# tridev.net
KiCad netlist of a schematic drawn in EAGLE
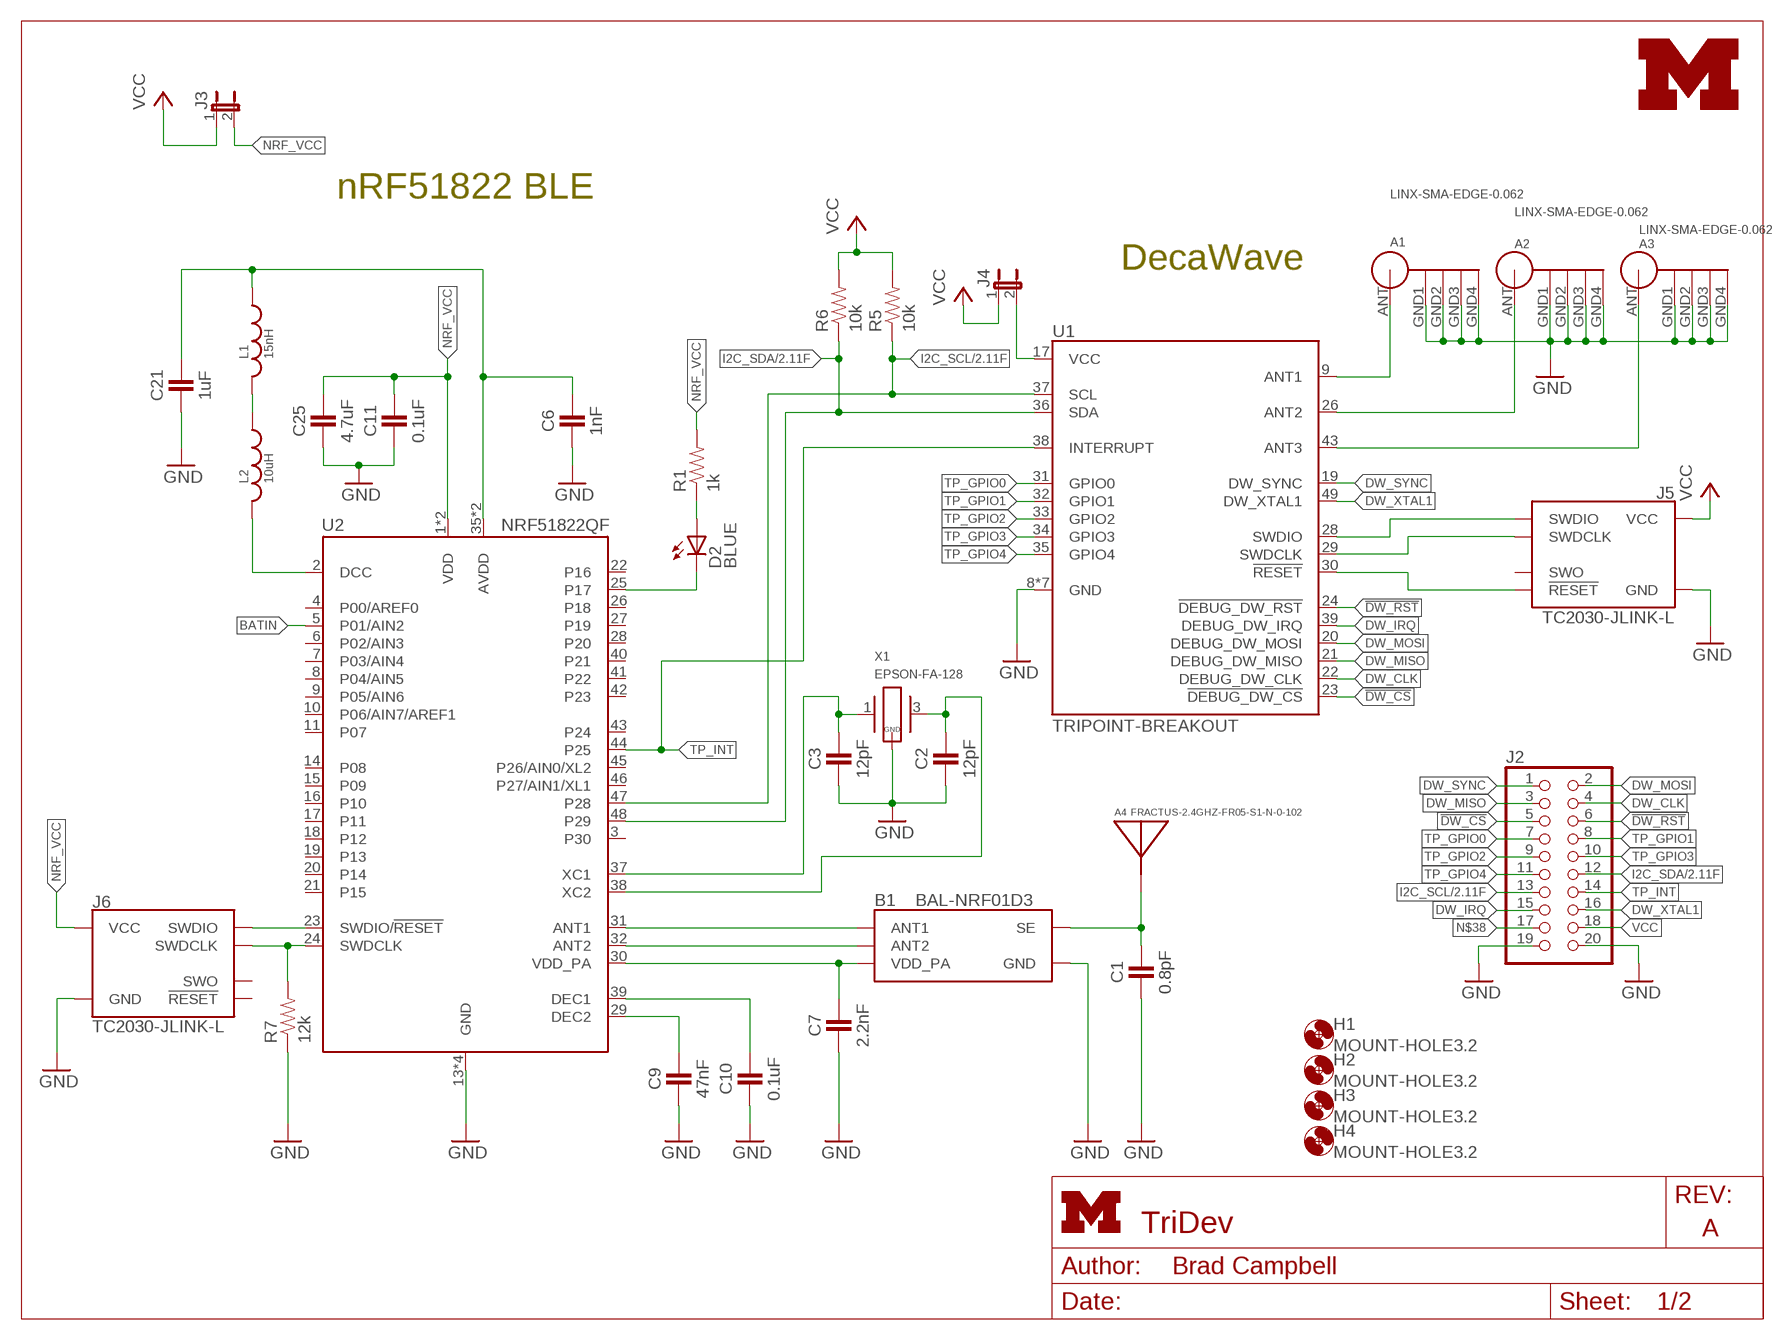
[diagram p0: schematic, sheet 1]
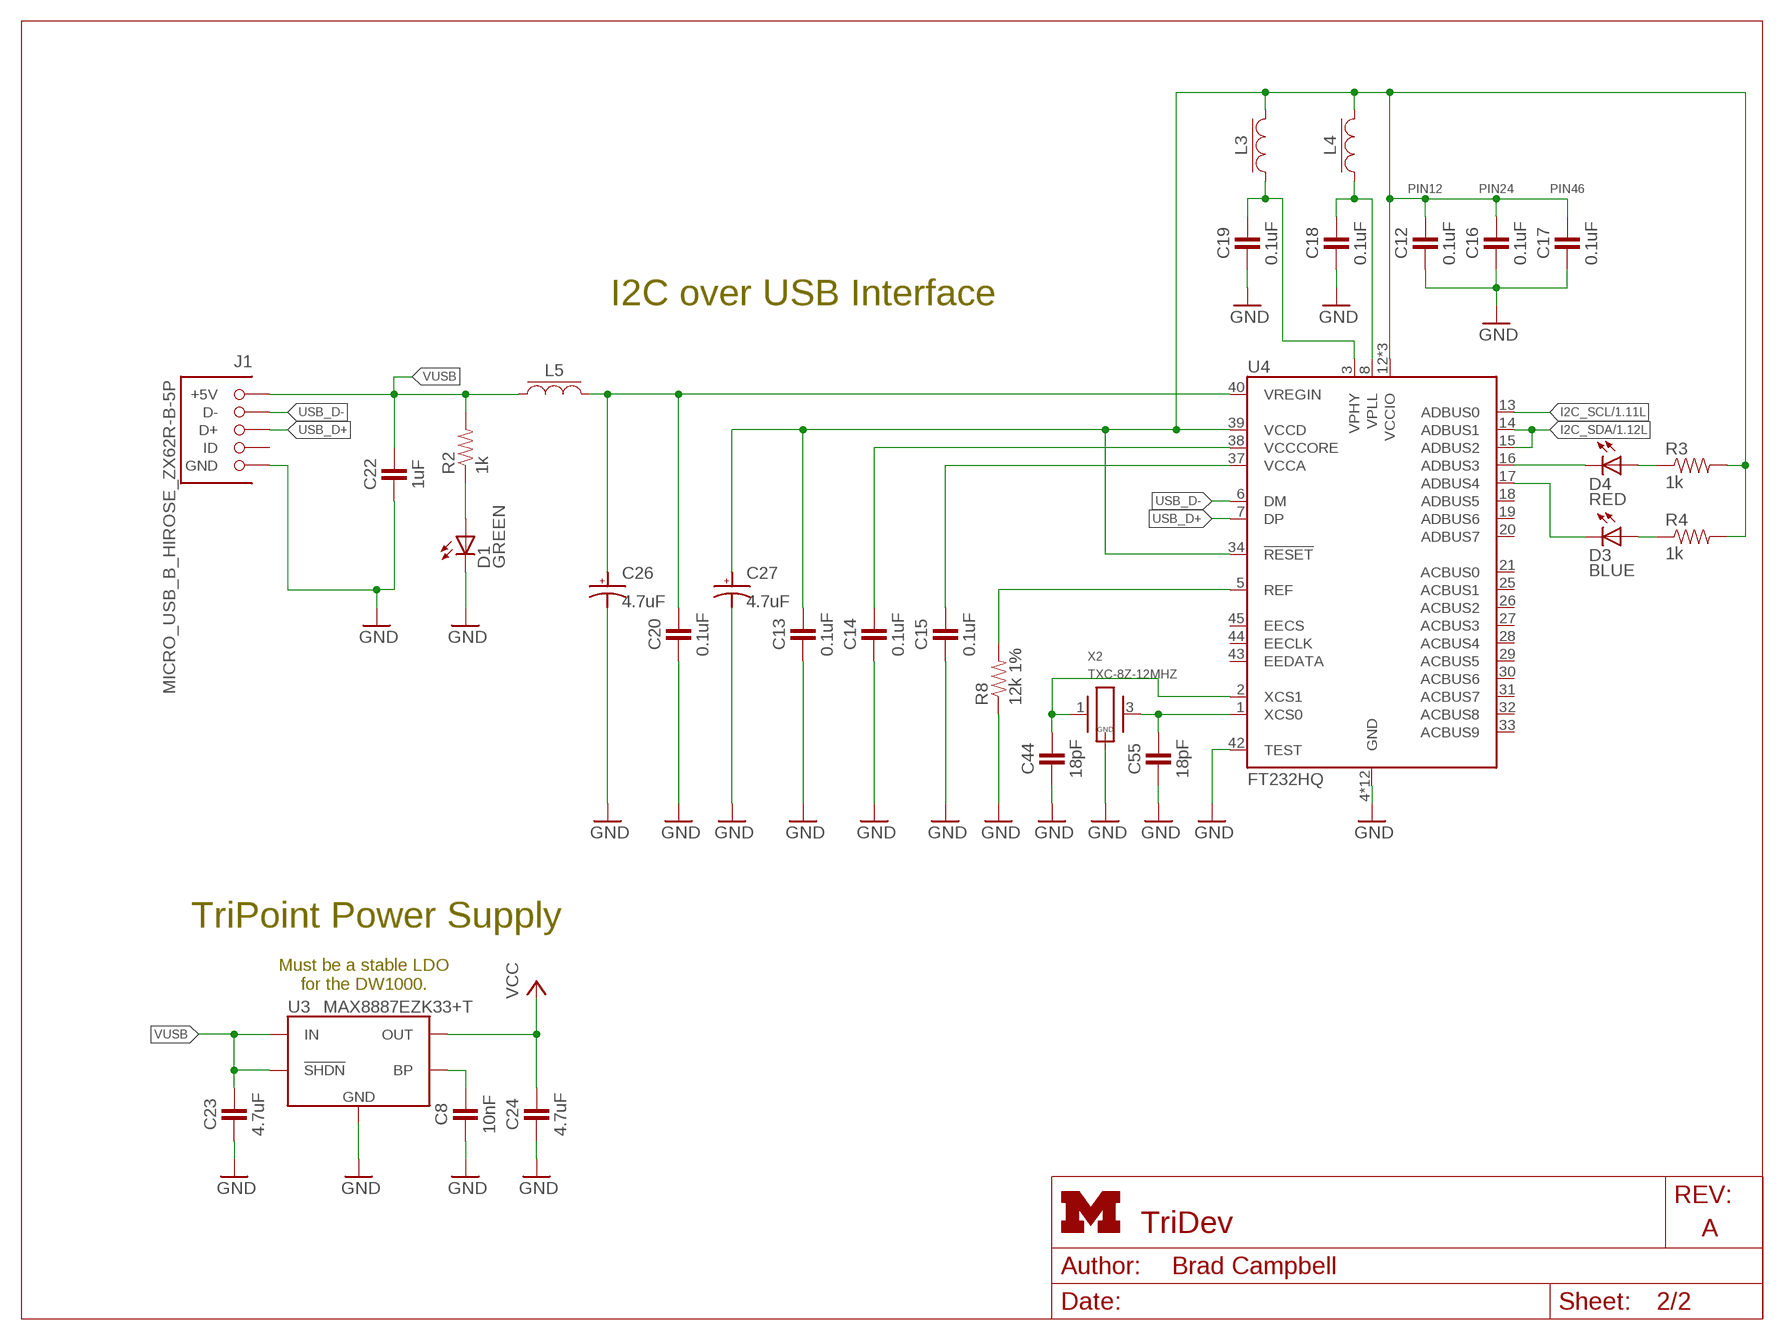
[diagram p1: schematic, sheet 2]

(export (version "E")
  (design (tool "Eeschema 10.0.6"))
  (components
    (comp (ref "A1")
      (value "LINX-SMA-EDGE-0.062")
      (footprint "eagle-import:CONSMA003.062")
      (libsource (lib "eagle-import") (part "LINX-SMA-EDGE-0.062"))
    )
    (comp (ref "A2")
      (value "LINX-SMA-EDGE-0.062")
      (footprint "eagle-import:CONSMA003.062")
      (libsource (lib "eagle-import") (part "LINX-SMA-EDGE-0.062"))
    )
    (comp (ref "A3")
      (value "LINX-SMA-EDGE-0.062")
      (footprint "eagle-import:CONSMA003.062")
      (libsource (lib "eagle-import") (part "LINX-SMA-EDGE-0.062"))
    )
    (comp (ref "A4")
      (value "FRACTUS-2.4GHZ-FR05-S1-N-0-102")
      (footprint "eagle-import:FRACTUS-ANTENNA-FR05-S1-N-0-102")
      (libsource (lib "eagle-import") (part "FRACTUS-2.4GHZ-FR05-S1-N-0-102"))
    )
    (comp (ref "B1")
      (value "BAL-NRF01D3")
      (footprint "eagle-import:BAL-NRF01D3")
      (libsource (lib "eagle-import") (part "BAL-NRF01D3"))
    )
    (comp (ref "C1")
      (value "0.8pF")
      (footprint "eagle-import:0402_CAP")
      (libsource (lib "eagle-import") (part "CAPACITOR"))
    )
    (comp (ref "C2")
      (value "12pF")
      (footprint "eagle-import:0402_CAP")
      (libsource (lib "eagle-import") (part "CAPACITOR"))
    )
    (comp (ref "C3")
      (value "12pF")
      (footprint "eagle-import:0402_CAP")
      (libsource (lib "eagle-import") (part "CAPACITOR"))
    )
    (comp (ref "C6")
      (value "1nF")
      (footprint "eagle-import:0402_CAP")
      (libsource (lib "eagle-import") (part "CAPACITOR"))
    )
    (comp (ref "C7")
      (value "2.2nF")
      (footprint "eagle-import:0402_CAP")
      (libsource (lib "eagle-import") (part "CAPACITOR"))
    )
    (comp (ref "C9")
      (value "47nF")
      (footprint "eagle-import:0402_CAP")
      (libsource (lib "eagle-import") (part "CAPACITOR"))
    )
    (comp (ref "C10")
      (value "0.1uF")
      (footprint "eagle-import:0402_CAP")
      (libsource (lib "eagle-import") (part "CAPACITOR"))
    )
    (comp (ref "C11")
      (value "0.1uF")
      (footprint "eagle-import:0402_CAP")
      (libsource (lib "eagle-import") (part "CAPACITOR"))
    )
    (comp (ref "C21")
      (value "1uF")
      (footprint "eagle-import:0402_CAP")
      (libsource (lib "eagle-import") (part "CAPACITOR"))
    )
    (comp (ref "C25")
      (value "4.7uF")
      (footprint "eagle-import:0402_CAP")
      (libsource (lib "eagle-import") (part "CAPACITOR"))
    )
    (comp (ref "D2")
      (value "BLUE")
      (footprint "eagle-import:LED-0603")
      (libsource (lib "eagle-import") (part "LED0603"))
    )
    (comp (ref "H1")
      (value "MOUNT-HOLE3.2")
      (footprint "eagle-import:3,2")
      (libsource (lib "eagle-import") (part "MOUNT-HOLE3.2"))
    )
    (comp (ref "H2")
      (value "MOUNT-HOLE3.2")
      (footprint "eagle-import:3,2")
      (libsource (lib "eagle-import") (part "MOUNT-HOLE3.2"))
    )
    (comp (ref "H3")
      (value "MOUNT-HOLE3.2")
      (footprint "eagle-import:3,2")
      (libsource (lib "eagle-import") (part "MOUNT-HOLE3.2"))
    )
    (comp (ref "H4")
      (value "MOUNT-HOLE3.2")
      (footprint "eagle-import:3,2")
      (libsource (lib "eagle-import") (part "MOUNT-HOLE3.2"))
    )
    (comp (ref "J2")
      (value "PINHD-2X10")
      (footprint "eagle-import:2X10")
      (libsource (lib "eagle-import") (part "PINHD-2X10"))
    )
    (comp (ref "J3")
      (value "JUMPER-2PTH")
      (footprint "eagle-import:1X02")
      (libsource (lib "eagle-import") (part "JUMPER-2PTH"))
    )
    (comp (ref "J4")
      (value "JUMPER-2PTH")
      (footprint "eagle-import:1X02")
      (libsource (lib "eagle-import") (part "JUMPER-2PTH"))
    )
    (comp (ref "J5")
      (value "TC2030-JLINK-L")
      (footprint "eagle-import:TC2030-IDC")
      (libsource (lib "eagle-import") (part "TC2030-JLINK-L"))
    )
    (comp (ref "J6")
      (value "TC2030-JLINK-L")
      (footprint "eagle-import:TC2030-IDC")
      (libsource (lib "eagle-import") (part "TC2030-JLINK-L"))
    )
    (comp (ref "L1")
      (value "15nH")
      (footprint "eagle-import:0402_CAP")
      (libsource (lib "eagle-import") (part "INDUCTOR0402"))
    )
    (comp (ref "L2")
      (value "10uH")
      (footprint "eagle-import:0603_CAP")
      (libsource (lib "eagle-import") (part "INDUCTOR0603"))
    )
    (comp (ref "LOGO1")
      (value "UMICH_SOLID_SMALL")
      (footprint "eagle-import:UMICH_SOLID_75MIL")
      (libsource (lib "eagle-import") (part "UMICH_SOLID_SMALL"))
    )
    (comp (ref "R1")
      (value "1k")
      (footprint "eagle-import:0402_RES")
      (libsource (lib "eagle-import") (part "RESISTOR0402_RES"))
    )
    (comp (ref "R5")
      (value "10k")
      (footprint "eagle-import:0402_RES")
      (libsource (lib "eagle-import") (part "RESISTOR0402_RES"))
    )
    (comp (ref "R6")
      (value "10k")
      (footprint "eagle-import:0402_RES")
      (libsource (lib "eagle-import") (part "RESISTOR0402_RES"))
    )
    (comp (ref "R7")
      (value "12k")
      (footprint "eagle-import:0402_RES")
      (libsource (lib "eagle-import") (part "RESISTOR0402_RES"))
    )
    (comp (ref "U1")
      (value "TRIPOINT-BREAKOUT")
      (footprint "eagle-import:TRIPOINT-BREAKOUT")
      (libsource (lib "eagle-import") (part "TRIPOINT-BREAKOUT"))
    )
    (comp (ref "U2")
      (value "NRF51822QF")
      (footprint "eagle-import:QFN-48-6MM")
      (libsource (lib "eagle-import") (part "NRF51822QF"))
    )
    (comp (ref "X1")
      (value "EPSON-FA-128")
      (footprint "eagle-import:FA-128")
      (libsource (lib "eagle-import") (part "EPSON-FA-128"))
    )
    (comp (ref "C8")
      (value "10nF")
      (footprint "eagle-import:0402_CAP")
      (libsource (lib "eagle-import") (part "CAPACITOR"))
    )
    (comp (ref "C12")
      (value "0.1uF")
      (footprint "eagle-import:0402_CAP")
      (libsource (lib "eagle-import") (part "CAPACITOR"))
    )
    (comp (ref "C13")
      (value "0.1uF")
      (footprint "eagle-import:0402_CAP")
      (libsource (lib "eagle-import") (part "CAPACITOR"))
    )
    (comp (ref "C14")
      (value "0.1uF")
      (footprint "eagle-import:0402_CAP")
      (libsource (lib "eagle-import") (part "CAPACITOR"))
    )
    (comp (ref "C15")
      (value "0.1uF")
      (footprint "eagle-import:0402_CAP")
      (libsource (lib "eagle-import") (part "CAPACITOR"))
    )
    (comp (ref "C16")
      (value "0.1uF")
      (footprint "eagle-import:0402_CAP")
      (libsource (lib "eagle-import") (part "CAPACITOR"))
    )
    (comp (ref "C17")
      (value "0.1uF")
      (footprint "eagle-import:0402_CAP")
      (libsource (lib "eagle-import") (part "CAPACITOR"))
    )
    (comp (ref "C18")
      (value "0.1uF")
      (footprint "eagle-import:0402_CAP")
      (libsource (lib "eagle-import") (part "CAPACITOR"))
    )
    (comp (ref "C19")
      (value "0.1uF")
      (footprint "eagle-import:0402_CAP")
      (libsource (lib "eagle-import") (part "CAPACITOR"))
    )
    (comp (ref "C20")
      (value "0.1uF")
      (footprint "eagle-import:0402_CAP")
      (libsource (lib "eagle-import") (part "CAPACITOR"))
    )
    (comp (ref "C22")
      (value "1uF")
      (footprint "eagle-import:0402_CAP")
      (libsource (lib "eagle-import") (part "CAPACITOR"))
    )
    (comp (ref "C23")
      (value "4.7uF")
      (footprint "eagle-import:0402_CAP")
      (libsource (lib "eagle-import") (part "CAPACITOR"))
    )
    (comp (ref "C24")
      (value "4.7uF")
      (footprint "eagle-import:0402_CAP")
      (libsource (lib "eagle-import") (part "CAPACITOR"))
    )
    (comp (ref "C26")
      (value "4.7uF")
      (footprint "eagle-import:CAP0603")
      (libsource (lib "eagle-import") (part "CAP_POL0603"))
    )
    (comp (ref "C27")
      (value "4.7uF")
      (footprint "eagle-import:CAP0603")
      (libsource (lib "eagle-import") (part "CAP_POL0603"))
    )
    (comp (ref "C44")
      (value "18pF")
      (footprint "eagle-import:0402_CAP")
      (libsource (lib "eagle-import") (part "CAPACITOR"))
    )
    (comp (ref "C55")
      (value "18pF")
      (footprint "eagle-import:0402_CAP")
      (libsource (lib "eagle-import") (part "CAPACITOR"))
    )
    (comp (ref "D1")
      (value "GREEN")
      (footprint "eagle-import:LED-0603")
      (libsource (lib "eagle-import") (part "LED0603"))
    )
    (comp (ref "D3")
      (value "BLUE")
      (footprint "eagle-import:LED-0603")
      (libsource (lib "eagle-import") (part "LED0603"))
    )
    (comp (ref "D4")
      (value "RED")
      (footprint "eagle-import:LED-0603")
      (libsource (lib "eagle-import") (part "LED0603"))
    )
    (comp (ref "J1")
      (value "MICRO_USB_B_HIROSE_ZX62R-B-5P")
      (footprint "eagle-import:USB_MICRO_B-HIROSE-ZX62R-B-5P")
      (libsource (lib "eagle-import") (part "MICRO_USB_B_HIROSE_ZX62R-B-5P"))
    )
    (comp (ref "L3")
      (value "FERRITE_BEAD")
      (footprint "eagle-import:0603_CAP")
      (libsource (lib "eagle-import") (part "FERRITE_BEAD"))
    )
    (comp (ref "L4")
      (value "FERRITE_BEAD")
      (footprint "eagle-import:0603_CAP")
      (libsource (lib "eagle-import") (part "FERRITE_BEAD"))
    )
    (comp (ref "L5")
      (value "FERRITE_BEAD")
      (footprint "eagle-import:0603_CAP")
      (libsource (lib "eagle-import") (part "FERRITE_BEAD"))
    )
    (comp (ref "R2")
      (value "1k")
      (footprint "eagle-import:0402_RES")
      (libsource (lib "eagle-import") (part "RESISTOR0402_RES"))
    )
    (comp (ref "R3")
      (value "1k")
      (footprint "eagle-import:0402_RES")
      (libsource (lib "eagle-import") (part "RESISTOR0402_RES"))
    )
    (comp (ref "R4")
      (value "1k")
      (footprint "eagle-import:0402_RES")
      (libsource (lib "eagle-import") (part "RESISTOR0402_RES"))
    )
    (comp (ref "R8")
      (value "12k 1%")
      (footprint "eagle-import:0402_RES")
      (libsource (lib "eagle-import") (part "RESISTOR0402_RES"))
    )
    (comp (ref "U3")
      (value "MAX8887EZK33+T")
      (footprint "eagle-import:SOT-23-5")
      (libsource (lib "eagle-import") (part "MAX8887EZK33+T"))
    )
    (comp (ref "U4")
      (value "FT232HQ")
      (footprint "eagle-import:QFN-48-8MM")
      (libsource (lib "eagle-import") (part "FT232HQ"))
    )
    (comp (ref "X2")
      (value "TXC-8Z-12MHZ")
      (footprint "eagle-import:TXC-8Z")
      (libsource (lib "eagle-import") (part "TXC-8Z-12MHZ"))
    )
  )
  (nets
    (net (code "1") (name "BATIN") (class "Default")
      (node (ref "U2") (pin "5") (pinfunction "P01/AIN2_5") (pintype "bidirectional"))
    )
    (net (code "2") (name "DW_CLK") (class "Default")
      (node (ref "J2") (pin "4") (pinfunction "4_4") (pintype "passive"))
      (node (ref "U1") (pin "22") (pinfunction "DEBUG_DW_CLK_22") (pintype "bidirectional"))
    )
    (net (code "3") (name "DW_IRQ") (class "Default")
      (node (ref "J2") (pin "15") (pinfunction "15_15") (pintype "passive"))
      (node (ref "U1") (pin "39") (pinfunction "DEBUG_DW_IRQ_39") (pintype "bidirectional"))
    )
    (net (code "4") (name "DW_MISO") (class "Default")
      (node (ref "J2") (pin "3") (pinfunction "3_3") (pintype "passive"))
      (node (ref "U1") (pin "21") (pinfunction "DEBUG_DW_MISO_21") (pintype "bidirectional"))
    )
    (net (code "5") (name "DW_MOSI") (class "Default")
      (node (ref "J2") (pin "2") (pinfunction "2_2") (pintype "passive"))
      (node (ref "U1") (pin "20") (pinfunction "DEBUG_DW_MOSI_20") (pintype "bidirectional"))
    )
    (net (code "6") (name "DW_SYNC") (class "Default")
      (node (ref "J2") (pin "1") (pinfunction "1_1") (pintype "passive"))
      (node (ref "U1") (pin "19") (pinfunction "DW_SYNC_19") (pintype "bidirectional"))
    )
    (net (code "7") (name "DW_XTAL1") (class "Default")
      (node (ref "J2") (pin "16") (pinfunction "16_16") (pintype "passive"))
      (node (ref "U1") (pin "49") (pinfunction "DW_XTAL1_49") (pintype "bidirectional"))
    )
    (net (code "8") (name "GND") (class "Default")
      (node (ref "A1") (pin "GND1") (pinfunction "P$2_GND1") (pintype "bidirectional"))
      (node (ref "A1") (pin "GND2") (pinfunction "P$3_GND2") (pintype "bidirectional"))
      (node (ref "A1") (pin "GND3") (pinfunction "P$4_GND3") (pintype "bidirectional"))
      (node (ref "A1") (pin "GND4") (pinfunction "P$5_GND4") (pintype "bidirectional"))
      (node (ref "A2") (pin "GND1") (pinfunction "P$2_GND1") (pintype "bidirectional"))
      (node (ref "A2") (pin "GND2") (pinfunction "P$3_GND2") (pintype "bidirectional"))
      (node (ref "A2") (pin "GND3") (pinfunction "P$4_GND3") (pintype "bidirectional"))
      (node (ref "A2") (pin "GND4") (pinfunction "P$5_GND4") (pintype "bidirectional"))
      (node (ref "A3") (pin "GND1") (pinfunction "P$2_GND1") (pintype "bidirectional"))
      (node (ref "A3") (pin "GND2") (pinfunction "P$3_GND2") (pintype "bidirectional"))
      (node (ref "A3") (pin "GND3") (pinfunction "P$4_GND3") (pintype "bidirectional"))
      (node (ref "A3") (pin "GND4") (pinfunction "P$5_GND4") (pintype "bidirectional"))
      (node (ref "B1") (pin "GND") (pinfunction "GND_GND") (pintype "bidirectional"))
      (node (ref "C1") (pin "2") (pinfunction "2_2") (pintype "bidirectional"))
      (node (ref "C10") (pin "2") (pinfunction "2_2") (pintype "bidirectional"))
      (node (ref "C11") (pin "2") (pinfunction "2_2") (pintype "bidirectional"))
      (node (ref "C12") (pin "2") (pinfunction "2_2") (pintype "bidirectional"))
      (node (ref "C13") (pin "2") (pinfunction "2_2") (pintype "bidirectional"))
      (node (ref "C14") (pin "2") (pinfunction "2_2") (pintype "bidirectional"))
      (node (ref "C15") (pin "2") (pinfunction "2_2") (pintype "bidirectional"))
      (node (ref "C16") (pin "2") (pinfunction "2_2") (pintype "bidirectional"))
      (node (ref "C17") (pin "2") (pinfunction "2_2") (pintype "bidirectional"))
      (node (ref "C18") (pin "2") (pinfunction "2_2") (pintype "bidirectional"))
      (node (ref "C19") (pin "2") (pinfunction "2_2") (pintype "bidirectional"))
      (node (ref "C2") (pin "2") (pinfunction "2_2") (pintype "bidirectional"))
      (node (ref "C20") (pin "2") (pinfunction "2_2") (pintype "bidirectional"))
      (node (ref "C21") (pin "2") (pinfunction "2_2") (pintype "bidirectional"))
      (node (ref "C22") (pin "2") (pinfunction "2_2") (pintype "bidirectional"))
      (node (ref "C23") (pin "2") (pinfunction "2_2") (pintype "bidirectional"))
      (node (ref "C24") (pin "2") (pinfunction "2_2") (pintype "bidirectional"))
      (node (ref "C25") (pin "2") (pinfunction "2_2") (pintype "bidirectional"))
      (node (ref "C26") (pin "NEG") (pinfunction "ANODE_NEG") (pintype "bidirectional"))
      (node (ref "C27") (pin "NEG") (pinfunction "ANODE_NEG") (pintype "bidirectional"))
      (node (ref "C3") (pin "2") (pinfunction "2_2") (pintype "bidirectional"))
      (node (ref "C44") (pin "2") (pinfunction "2_2") (pintype "bidirectional"))
      (node (ref "C55") (pin "2") (pinfunction "2_2") (pintype "bidirectional"))
      (node (ref "C6") (pin "2") (pinfunction "2_2") (pintype "bidirectional"))
      (node (ref "C7") (pin "2") (pinfunction "2_2") (pintype "bidirectional"))
      (node (ref "C8") (pin "2") (pinfunction "2_2") (pintype "bidirectional"))
      (node (ref "C9") (pin "2") (pinfunction "2_2") (pintype "bidirectional"))
      (node (ref "D1") (pin "C") (pinfunction "C_C") (pintype "passive"))
      (node (ref "J1") (pin "5") (pinfunction "GND_5") (pintype "bidirectional"))
      (node (ref "J2") (pin "19") (pinfunction "19_19") (pintype "passive"))
      (node (ref "J2") (pin "20") (pinfunction "20_20") (pintype "passive"))
      (node (ref "J5") (pin "5") (pinfunction "GND_5") (pintype "bidirectional"))
      (node (ref "J6") (pin "5") (pinfunction "GND_5") (pintype "bidirectional"))
      (node (ref "R7") (pin "1") (pinfunction "1_1") (pintype "passive"))
      (node (ref "R8") (pin "1") (pinfunction "1_1") (pintype "passive"))
      (node (ref "U1") (pin "10") (pinfunction "GND_10") (pintype "bidirectional"))
      (node (ref "U1") (pin "18") (pinfunction "GND_18") (pintype "bidirectional"))
      (node (ref "U1") (pin "25") (pinfunction "GND_25") (pintype "bidirectional"))
      (node (ref "U1") (pin "27") (pinfunction "GND_27") (pintype "bidirectional"))
      (node (ref "U1") (pin "42") (pinfunction "GND_42") (pintype "bidirectional"))
      (node (ref "U1") (pin "44") (pinfunction "GND_44") (pintype "bidirectional"))
      (node (ref "U1") (pin "8") (pinfunction "GND_8") (pintype "bidirectional"))
      (node (ref "U2") (pin "13") (pinfunction "GND_13") (pintype "bidirectional"))
      (node (ref "U2") (pin "33") (pinfunction "GND_33") (pintype "bidirectional"))
      (node (ref "U2") (pin "34") (pinfunction "GND_34") (pintype "bidirectional"))
      (node (ref "U2") (pin "GND") (pinfunction "GND_GND") (pintype "bidirectional"))
      (node (ref "U3") (pin "2") (pinfunction "GND_2") (pintype "bidirectional"))
      (node (ref "U4") (pin "10") (pinfunction "GND_10") (pintype "bidirectional"))
      (node (ref "U4") (pin "11") (pinfunction "GND_11") (pintype "bidirectional"))
      (node (ref "U4") (pin "22") (pinfunction "GND_22") (pintype "bidirectional"))
      (node (ref "U4") (pin "23") (pinfunction "GND_23") (pintype "bidirectional"))
      (node (ref "U4") (pin "35") (pinfunction "GND_35") (pintype "bidirectional"))
      (node (ref "U4") (pin "36") (pinfunction "GND_36") (pintype "bidirectional"))
      (node (ref "U4") (pin "4") (pinfunction "GND_4") (pintype "bidirectional"))
      (node (ref "U4") (pin "41") (pinfunction "GND_41") (pintype "bidirectional"))
      (node (ref "U4") (pin "42") (pinfunction "TEST_42") (pintype "bidirectional"))
      (node (ref "U4") (pin "47") (pinfunction "GND_47") (pintype "bidirectional"))
      (node (ref "U4") (pin "48") (pinfunction "GND_48") (pintype "bidirectional"))
      (node (ref "U4") (pin "9") (pinfunction "GND_9") (pintype "bidirectional"))
      (node (ref "U4") (pin "PAD") (pinfunction "GND_PAD") (pintype "bidirectional"))
      (node (ref "X1") (pin "2") (pinfunction "GND_2") (pintype "bidirectional"))
      (node (ref "X1") (pin "4") (pinfunction "GND_4") (pintype "bidirectional"))
      (node (ref "X2") (pin "2") (pinfunction "GND_2") (pintype "bidirectional"))
      (node (ref "X2") (pin "4") (pinfunction "GND_4") (pintype "bidirectional"))
    )
    (net (code "9") (name "I2C_SCL") (class "Default")
      (node (ref "J2") (pin "13") (pinfunction "13_13") (pintype "passive"))
      (node (ref "R5") (pin "1") (pinfunction "1_1") (pintype "passive"))
      (node (ref "U1") (pin "37") (pinfunction "SCL_37") (pintype "bidirectional"))
      (node (ref "U2") (pin "47") (pinfunction "P28_47") (pintype "bidirectional"))
      (node (ref "U4") (pin "13") (pinfunction "ADBUS0_13") (pintype "bidirectional"))
    )
    (net (code "10") (name "I2C_SDA") (class "Default")
      (node (ref "J2") (pin "12") (pinfunction "12_12") (pintype "passive"))
      (node (ref "R6") (pin "1") (pinfunction "1_1") (pintype "passive"))
      (node (ref "U1") (pin "36") (pinfunction "SDA_36") (pintype "bidirectional"))
      (node (ref "U2") (pin "48") (pinfunction "P29_48") (pintype "bidirectional"))
      (node (ref "U4") (pin "14") (pinfunction "ADBUS1_14") (pintype "bidirectional"))
      (node (ref "U4") (pin "15") (pinfunction "ADBUS2_15") (pintype "bidirectional"))
    )
    (net (code "11") (name "N$38") (class "Default")
      (node (ref "J2") (pin "17") (pinfunction "17_17") (pintype "passive"))
    )
    (net (code "12") (name "NRF_VCC") (class "Default")
      (node (ref "C11") (pin "1") (pinfunction "1_1") (pintype "bidirectional"))
      (node (ref "C25") (pin "1") (pinfunction "1_1") (pintype "bidirectional"))
      (node (ref "J3") (pin "2") (pinfunction "2_2") (pintype "passive"))
      (node (ref "J6") (pin "1") (pinfunction "VCC_1") (pintype "bidirectional"))
      (node (ref "R1") (pin "2") (pinfunction "2_2") (pintype "passive"))
      (node (ref "U2") (pin "1") (pinfunction "VDD_1") (pintype "bidirectional"))
      (node (ref "U2") (pin "12") (pinfunction "VDD_12") (pintype "bidirectional"))
    )
    (net (code "13") (name "Net-(A4-ANTENNA)") (class "Default")
      (node (ref "A4") (pin "1") (pinfunction "ANTENNA_1") (pintype "bidirectional"))
      (node (ref "B1") (pin "SE") (pinfunction "SE_SE") (pintype "bidirectional"))
      (node (ref "C1") (pin "1") (pinfunction "1_1") (pintype "bidirectional"))
    )
    (net (code "14") (name "Net-(B1-VDD_PA)") (class "Default")
      (node (ref "B1") (pin "VCC") (pinfunction "VDD_PA_VCC") (pintype "bidirectional"))
      (node (ref "C7") (pin "1") (pinfunction "1_1") (pintype "bidirectional"))
      (node (ref "U2") (pin "30") (pinfunction "VDD_PA_30") (pintype "bidirectional"))
    )
    (net (code "15") (name "Net-(C21-Pad1)") (class "Default")
      (node (ref "C21") (pin "1") (pinfunction "1_1") (pintype "bidirectional"))
      (node (ref "C6") (pin "1") (pinfunction "1_1") (pintype "bidirectional"))
      (node (ref "L1") (pin "1") (pinfunction "1_1") (pintype "bidirectional"))
      (node (ref "U2") (pin "35") (pinfunction "AVDD_35") (pintype "bidirectional"))
      (node (ref "U2") (pin "36") (pinfunction "AVDD_36") (pintype "bidirectional"))
    )
    (net (code "16") (name "Net-(C26-CATHODE)") (class "Default")
      (node (ref "C20") (pin "1") (pinfunction "1_1") (pintype "bidirectional"))
      (node (ref "C26") (pin "POS") (pinfunction "CATHODE_POS") (pintype "bidirectional"))
      (node (ref "L5") (pin "2") (pinfunction "P$2_2") (pintype "bidirectional"))
      (node (ref "U4") (pin "40") (pinfunction "VREGIN_40") (pintype "bidirectional"))
    )
    (net (code "17") (name "Net-(C27-CATHODE)") (class "Default")
      (node (ref "C12") (pin "1") (pinfunction "1_1") (pintype "bidirectional"))
      (node (ref "C13") (pin "1") (pinfunction "1_1") (pintype "bidirectional"))
      (node (ref "C16") (pin "1") (pinfunction "1_1") (pintype "bidirectional"))
      (node (ref "C17") (pin "1") (pinfunction "1_1") (pintype "bidirectional"))
      (node (ref "C27") (pin "POS") (pinfunction "CATHODE_POS") (pintype "bidirectional"))
      (node (ref "L3") (pin "2") (pinfunction "P$2_2") (pintype "bidirectional"))
      (node (ref "L4") (pin "2") (pinfunction "P$2_2") (pintype "bidirectional"))
      (node (ref "R3") (pin "2") (pinfunction "2_2") (pintype "passive"))
      (node (ref "R4") (pin "2") (pinfunction "2_2") (pintype "passive"))
      (node (ref "U4") (pin "12") (pinfunction "VCCIO_12") (pintype "bidirectional"))
      (node (ref "U4") (pin "24") (pinfunction "VCCIO_24") (pintype "bidirectional"))
      (node (ref "U4") (pin "34") (pinfunction "~{RESET}_34") (pintype "bidirectional"))
      (node (ref "U4") (pin "39") (pinfunction "VCCD_39") (pintype "bidirectional"))
      (node (ref "U4") (pin "46") (pinfunction "VCCIO_46") (pintype "bidirectional"))
    )
    (net (code "18") (name "Net-(D1-PadA)") (class "Default")
      (node (ref "D1") (pin "A") (pinfunction "A_A") (pintype "passive"))
      (node (ref "R2") (pin "1") (pinfunction "1_1") (pintype "passive"))
    )
    (net (code "19") (name "Net-(D2-PadA)") (class "Default")
      (node (ref "D2") (pin "A") (pinfunction "A_A") (pintype "passive"))
      (node (ref "R1") (pin "1") (pinfunction "1_1") (pintype "passive"))
    )
    (net (code "20") (name "Net-(D3-PadA)") (class "Default")
      (node (ref "D3") (pin "A") (pinfunction "A_A") (pintype "passive"))
      (node (ref "R4") (pin "1") (pinfunction "1_1") (pintype "passive"))
    )
    (net (code "21") (name "Net-(D4-PadA)") (class "Default")
      (node (ref "D4") (pin "A") (pinfunction "A_A") (pintype "passive"))
      (node (ref "R3") (pin "1") (pinfunction "1_1") (pintype "passive"))
    )
    (net (code "22") (name "Net-(J5-SWDCLK)") (class "Default")
      (node (ref "J5") (pin "4") (pinfunction "SWDCLK_4") (pintype "bidirectional"))
      (node (ref "U1") (pin "29") (pinfunction "SWDCLK_29") (pintype "bidirectional"))
    )
    (net (code "23") (name "Net-(J5-SWDIO)") (class "Default")
      (node (ref "J5") (pin "2") (pinfunction "SWDIO_2") (pintype "bidirectional"))
      (node (ref "U1") (pin "28") (pinfunction "SWDIO_28") (pintype "bidirectional"))
    )
    (net (code "24") (name "Net-(J5-~{RESET})") (class "Default")
      (node (ref "J5") (pin "3") (pinfunction "~{RESET}_3") (pintype "bidirectional"))
      (node (ref "U1") (pin "30") (pinfunction "~{RESET}_30") (pintype "bidirectional"))
    )
    (net (code "25") (name "Net-(J6-SWDCLK)") (class "Default")
      (node (ref "J6") (pin "4") (pinfunction "SWDCLK_4") (pintype "bidirectional"))
      (node (ref "R7") (pin "2") (pinfunction "2_2") (pintype "passive"))
      (node (ref "U2") (pin "24") (pinfunction "SWDCLK_24") (pintype "bidirectional"))
    )
    (net (code "26") (name "Net-(J6-SWDIO)") (class "Default")
      (node (ref "J6") (pin "2") (pinfunction "SWDIO_2") (pintype "bidirectional"))
      (node (ref "U2") (pin "23") (pinfunction "SWDIO/~{RESET}_23") (pintype "bidirectional"))
    )
    (net (code "27") (name "Net-(L1-Pad2)") (class "Default")
      (node (ref "L1") (pin "2") (pinfunction "2_2") (pintype "bidirectional"))
      (node (ref "L2") (pin "1") (pinfunction "1_1") (pintype "bidirectional"))
    )
    (net (code "28") (name "Net-(L3-P$1)") (class "Default")
      (node (ref "C19") (pin "1") (pinfunction "1_1") (pintype "bidirectional"))
      (node (ref "L3") (pin "1") (pinfunction "P$1_1") (pintype "bidirectional"))
      (node (ref "U4") (pin "3") (pinfunction "VPHY_3") (pintype "bidirectional"))
    )
    (net (code "29") (name "Net-(L4-P$1)") (class "Default")
      (node (ref "C18") (pin "1") (pinfunction "1_1") (pintype "bidirectional"))
      (node (ref "L4") (pin "1") (pinfunction "P$1_1") (pintype "bidirectional"))
      (node (ref "U4") (pin "8") (pinfunction "VPLL_8") (pintype "bidirectional"))
    )
    (net (code "30") (name "Net-(U1-ANT1)") (class "Default")
      (node (ref "A1") (pin "ANT") (pinfunction "ANT_ANT") (pintype "bidirectional"))
      (node (ref "U1") (pin "9") (pinfunction "ANT1_9") (pintype "bidirectional"))
    )
    (net (code "31") (name "Net-(U1-ANT2)") (class "Default")
      (node (ref "A2") (pin "ANT") (pinfunction "ANT_ANT") (pintype "bidirectional"))
      (node (ref "U1") (pin "26") (pinfunction "ANT2_26") (pintype "bidirectional"))
    )
    (net (code "32") (name "Net-(U1-ANT3)") (class "Default")
      (node (ref "A3") (pin "ANT") (pinfunction "ANT_ANT") (pintype "bidirectional"))
      (node (ref "U1") (pin "43") (pinfunction "ANT3_43") (pintype "bidirectional"))
    )
    (net (code "33") (name "Net-(U1-VCC)") (class "Default")
      (node (ref "J4") (pin "2") (pinfunction "2_2") (pintype "passive"))
      (node (ref "U1") (pin "17") (pinfunction "VCC_17") (pintype "bidirectional"))
    )
    (net (code "34") (name "Net-(U2-ANT1)") (class "Default")
      (node (ref "B1") (pin "ANT1") (pinfunction "ANT1_ANT1") (pintype "bidirectional"))
      (node (ref "U2") (pin "31") (pinfunction "ANT1_31") (pintype "bidirectional"))
    )
    (net (code "35") (name "Net-(U2-ANT2)") (class "Default")
      (node (ref "B1") (pin "ANT2") (pinfunction "ANT2_ANT2") (pintype "bidirectional"))
      (node (ref "U2") (pin "32") (pinfunction "ANT2_32") (pintype "bidirectional"))
    )
    (net (code "36") (name "Net-(U2-DCC)") (class "Default")
      (node (ref "L2") (pin "2") (pinfunction "2_2") (pintype "bidirectional"))
      (node (ref "U2") (pin "2") (pinfunction "DCC_2") (pintype "bidirectional"))
    )
    (net (code "37") (name "Net-(U2-DEC1)") (class "Default")
      (node (ref "C10") (pin "1") (pinfunction "1_1") (pintype "bidirectional"))
      (node (ref "U2") (pin "39") (pinfunction "DEC1_39") (pintype "bidirectional"))
    )
    (net (code "38") (name "Net-(U2-DEC2)") (class "Default")
      (node (ref "C9") (pin "1") (pinfunction "1_1") (pintype "bidirectional"))
      (node (ref "U2") (pin "29") (pinfunction "DEC2_29") (pintype "bidirectional"))
    )
    (net (code "39") (name "Net-(U2-P17)") (class "Default")
      (node (ref "D2") (pin "C") (pinfunction "C_C") (pintype "passive"))
      (node (ref "U2") (pin "25") (pinfunction "P17_25") (pintype "bidirectional"))
    )
    (net (code "40") (name "Net-(U2-XC1)") (class "Default")
      (node (ref "C3") (pin "1") (pinfunction "1_1") (pintype "bidirectional"))
      (node (ref "U2") (pin "37") (pinfunction "XC1_37") (pintype "bidirectional"))
      (node (ref "X1") (pin "1") (pinfunction "1_1") (pintype "bidirectional"))
    )
    (net (code "41") (name "Net-(U2-XC2)") (class "Default")
      (node (ref "C2") (pin "1") (pinfunction "1_1") (pintype "bidirectional"))
      (node (ref "U2") (pin "38") (pinfunction "XC2_38") (pintype "bidirectional"))
      (node (ref "X1") (pin "3") (pinfunction "2_3") (pintype "bidirectional"))
    )
    (net (code "42") (name "Net-(U3-BP)") (class "Default")
      (node (ref "C8") (pin "1") (pinfunction "1_1") (pintype "bidirectional"))
      (node (ref "U3") (pin "4") (pinfunction "BP_4") (pintype "bidirectional"))
    )
    (net (code "43") (name "Net-(U4-ADBUS3)") (class "Default")
      (node (ref "D4") (pin "C") (pinfunction "C_C") (pintype "passive"))
      (node (ref "U4") (pin "16") (pinfunction "ADBUS3_16") (pintype "bidirectional"))
    )
    (net (code "44") (name "Net-(U4-ADBUS4)") (class "Default")
      (node (ref "D3") (pin "C") (pinfunction "C_C") (pintype "passive"))
      (node (ref "U4") (pin "17") (pinfunction "ADBUS4_17") (pintype "bidirectional"))
    )
    (net (code "45") (name "Net-(U4-REF)") (class "Default")
      (node (ref "R8") (pin "2") (pinfunction "2_2") (pintype "passive"))
      (node (ref "U4") (pin "5") (pinfunction "REF_5") (pintype "bidirectional"))
    )
    (net (code "46") (name "Net-(U4-VCCA)") (class "Default")
      (node (ref "C15") (pin "1") (pinfunction "1_1") (pintype "bidirectional"))
      (node (ref "U4") (pin "37") (pinfunction "VCCA_37") (pintype "bidirectional"))
    )
    (net (code "47") (name "Net-(U4-VCCCORE)") (class "Default")
      (node (ref "C14") (pin "1") (pinfunction "1_1") (pintype "bidirectional"))
      (node (ref "U4") (pin "38") (pinfunction "VCCCORE_38") (pintype "bidirectional"))
    )
    (net (code "48") (name "Net-(U4-XCS0)") (class "Default")
      (node (ref "C55") (pin "1") (pinfunction "1_1") (pintype "bidirectional"))
      (node (ref "U4") (pin "1") (pinfunction "XCS0_1") (pintype "bidirectional"))
      (node (ref "X2") (pin "3") (pinfunction "2_3") (pintype "bidirectional"))
    )
    (net (code "49") (name "Net-(U4-XCS1)") (class "Default")
      (node (ref "C44") (pin "1") (pinfunction "1_1") (pintype "bidirectional"))
      (node (ref "U4") (pin "2") (pinfunction "XCS1_2") (pintype "bidirectional"))
      (node (ref "X2") (pin "1") (pinfunction "1_1") (pintype "bidirectional"))
    )
    (net (code "50") (name "TP_GPIO0") (class "Default")
      (node (ref "J2") (pin "7") (pinfunction "7_7") (pintype "passive"))
      (node (ref "U1") (pin "31") (pinfunction "GPIO0_31") (pintype "bidirectional"))
    )
    (net (code "51") (name "TP_GPIO1") (class "Default")
      (node (ref "J2") (pin "8") (pinfunction "8_8") (pintype "passive"))
      (node (ref "U1") (pin "32") (pinfunction "GPIO1_32") (pintype "bidirectional"))
    )
    (net (code "52") (name "TP_GPIO2") (class "Default")
      (node (ref "J2") (pin "9") (pinfunction "9_9") (pintype "passive"))
      (node (ref "U1") (pin "33") (pinfunction "GPIO2_33") (pintype "bidirectional"))
    )
    (net (code "53") (name "TP_GPIO3") (class "Default")
      (node (ref "J2") (pin "10") (pinfunction "10_10") (pintype "passive"))
      (node (ref "U1") (pin "34") (pinfunction "GPIO3_34") (pintype "bidirectional"))
    )
    (net (code "54") (name "TP_GPIO4") (class "Default")
      (node (ref "J2") (pin "11") (pinfunction "11_11") (pintype "passive"))
      (node (ref "U1") (pin "35") (pinfunction "GPIO4_35") (pintype "bidirectional"))
    )
    (net (code "55") (name "TP_INT") (class "Default")
      (node (ref "J2") (pin "14") (pinfunction "14_14") (pintype "passive"))
      (node (ref "U1") (pin "38") (pinfunction "INTERRUPT_38") (pintype "bidirectional"))
      (node (ref "U2") (pin "44") (pinfunction "P25_44") (pintype "bidirectional"))
    )
    (net (code "56") (name "USB_D+") (class "Default")
      (node (ref "J1") (pin "3") (pinfunction "D+_3") (pintype "bidirectional"))
      (node (ref "U4") (pin "7") (pinfunction "DP_7") (pintype "bidirectional"))
    )
    (net (code "57") (name "USB_D-") (class "Default")
      (node (ref "J1") (pin "2") (pinfunction "D-_2") (pintype "bidirectional"))
      (node (ref "U4") (pin "6") (pinfunction "DM_6") (pintype "bidirectional"))
    )
    (net (code "58") (name "VCC") (class "Default")
      (node (ref "C24") (pin "1") (pinfunction "1_1") (pintype "bidirectional"))
      (node (ref "J2") (pin "18") (pinfunction "18_18") (pintype "passive"))
      (node (ref "J3") (pin "1") (pinfunction "1_1") (pintype "passive"))
      (node (ref "J4") (pin "1") (pinfunction "1_1") (pintype "passive"))
      (node (ref "J5") (pin "1") (pinfunction "VCC_1") (pintype "bidirectional"))
      (node (ref "R5") (pin "2") (pinfunction "2_2") (pintype "passive"))
      (node (ref "R6") (pin "2") (pinfunction "2_2") (pintype "passive"))
      (node (ref "U3") (pin "5") (pinfunction "OUT_5") (pintype "bidirectional"))
    )
    (net (code "59") (name "VUSB") (class "Default")
      (node (ref "C22") (pin "1") (pinfunction "1_1") (pintype "bidirectional"))
      (node (ref "C23") (pin "1") (pinfunction "1_1") (pintype "bidirectional"))
      (node (ref "J1") (pin "1") (pinfunction "+5V_1") (pintype "bidirectional"))
      (node (ref "L5") (pin "1") (pinfunction "P$1_1") (pintype "bidirectional"))
      (node (ref "R2") (pin "2") (pinfunction "2_2") (pintype "passive"))
      (node (ref "U3") (pin "1") (pinfunction "IN_1") (pintype "bidirectional"))
      (node (ref "U3") (pin "3") (pinfunction "~{SHDN}_3") (pintype "bidirectional"))
    )
    (net (code "60") (name "unconnected-(J1-ID-Pad4)") (class "Default")
      (node (ref "J1") (pin "4") (pinfunction "ID_4") (pintype "bidirectional"))
    )
    (net (code "61") (name "unconnected-(J5-SWO-Pad6)") (class "Default")
      (node (ref "J5") (pin "6") (pinfunction "SWO_6") (pintype "bidirectional"))
    )
    (net (code "62") (name "unconnected-(J6-SWO-Pad6)") (class "Default")
      (node (ref "J6") (pin "6") (pinfunction "SWO_6") (pintype "bidirectional"))
    )
    (net (code "63") (name "unconnected-(J6-~{RESET}-Pad3)") (class "Default")
      (node (ref "J6") (pin "3") (pinfunction "~{RESET}_3") (pintype "bidirectional"))
    )
    (net (code "64") (name "unconnected-(U2-P00{slash}AREF0-Pad4)") (class "Default")
      (node (ref "U2") (pin "4") (pinfunction "P00/AREF0_4") (pintype "bidirectional"))
    )
    (net (code "65") (name "unconnected-(U2-P02{slash}AIN3-Pad6)") (class "Default")
      (node (ref "U2") (pin "6") (pinfunction "P02/AIN3_6") (pintype "bidirectional"))
    )
    (net (code "66") (name "unconnected-(U2-P03{slash}AIN4-Pad7)") (class "Default")
      (node (ref "U2") (pin "7") (pinfunction "P03/AIN4_7") (pintype "bidirectional"))
    )
    (net (code "67") (name "unconnected-(U2-P04{slash}AIN5-Pad8)") (class "Default")
      (node (ref "U2") (pin "8") (pinfunction "P04/AIN5_8") (pintype "bidirectional"))
    )
    (net (code "68") (name "unconnected-(U2-P05{slash}AIN6-Pad9)") (class "Default")
      (node (ref "U2") (pin "9") (pinfunction "P05/AIN6_9") (pintype "bidirectional"))
    )
    (net (code "69") (name "unconnected-(U2-P06{slash}AIN7{slash}AREF1-Pad10)") (class "Default")
      (node (ref "U2") (pin "10") (pinfunction "P06/AIN7/AREF1_10") (pintype "bidirectional"))
    )
    (net (code "70") (name "unconnected-(U2-P07-Pad11)") (class "Default")
      (node (ref "U2") (pin "11") (pinfunction "P07_11") (pintype "bidirectional"))
    )
    (net (code "71") (name "unconnected-(U2-P08-Pad14)") (class "Default")
      (node (ref "U2") (pin "14") (pinfunction "P08_14") (pintype "bidirectional"))
    )
    (net (code "72") (name "unconnected-(U2-P09-Pad15)") (class "Default")
      (node (ref "U2") (pin "15") (pinfunction "P09_15") (pintype "bidirectional"))
    )
    (net (code "73") (name "unconnected-(U2-P10-Pad16)") (class "Default")
      (node (ref "U2") (pin "16") (pinfunction "P10_16") (pintype "bidirectional"))
    )
    (net (code "74") (name "unconnected-(U2-P11-Pad17)") (class "Default")
      (node (ref "U2") (pin "17") (pinfunction "P11_17") (pintype "bidirectional"))
    )
    (net (code "75") (name "unconnected-(U2-P12-Pad18)") (class "Default")
      (node (ref "U2") (pin "18") (pinfunction "P12_18") (pintype "bidirectional"))
    )
    (net (code "76") (name "unconnected-(U2-P13-Pad19)") (class "Default")
      (node (ref "U2") (pin "19") (pinfunction "P13_19") (pintype "bidirectional"))
    )
    (net (code "77") (name "unconnected-(U2-P14-Pad20)") (class "Default")
      (node (ref "U2") (pin "20") (pinfunction "P14_20") (pintype "bidirectional"))
    )
    (net (code "78") (name "unconnected-(U2-P15-Pad21)") (class "Default")
      (node (ref "U2") (pin "21") (pinfunction "P15_21") (pintype "bidirectional"))
    )
    (net (code "79") (name "unconnected-(U2-P16-Pad22)") (class "Default")
      (node (ref "U2") (pin "22") (pinfunction "P16_22") (pintype "bidirectional"))
    )
    (net (code "80") (name "unconnected-(U2-P18-Pad26)") (class "Default")
      (node (ref "U2") (pin "26") (pinfunction "P18_26") (pintype "bidirectional"))
    )
    (net (code "81") (name "unconnected-(U2-P19-Pad27)") (class "Default")
      (node (ref "U2") (pin "27") (pinfunction "P19_27") (pintype "bidirectional"))
    )
    (net (code "82") (name "unconnected-(U2-P20-Pad28)") (class "Default")
      (node (ref "U2") (pin "28") (pinfunction "P20_28") (pintype "bidirectional"))
    )
    (net (code "83") (name "unconnected-(U2-P21-Pad40)") (class "Default")
      (node (ref "U2") (pin "40") (pinfunction "P21_40") (pintype "bidirectional"))
    )
    (net (code "84") (name "unconnected-(U2-P22-Pad41)") (class "Default")
      (node (ref "U2") (pin "41") (pinfunction "P22_41") (pintype "bidirectional"))
    )
    (net (code "85") (name "unconnected-(U2-P23-Pad42)") (class "Default")
      (node (ref "U2") (pin "42") (pinfunction "P23_42") (pintype "bidirectional"))
    )
    (net (code "86") (name "unconnected-(U2-P24-Pad43)") (class "Default")
      (node (ref "U2") (pin "43") (pinfunction "P24_43") (pintype "bidirectional"))
    )
    (net (code "87") (name "unconnected-(U2-P26{slash}AIN0{slash}XL2-Pad45)") (class "Default")
      (node (ref "U2") (pin "45") (pinfunction "P26/AIN0/XL2_45") (pintype "bidirectional"))
    )
    (net (code "88") (name "unconnected-(U2-P27{slash}AIN1{slash}XL1-Pad46)") (class "Default")
      (node (ref "U2") (pin "46") (pinfunction "P27/AIN1/XL1_46") (pintype "bidirectional"))
    )
    (net (code "89") (name "unconnected-(U2-P30-Pad3)") (class "Default")
      (node (ref "U2") (pin "3") (pinfunction "P30_3") (pintype "bidirectional"))
    )
    (net (code "90") (name "unconnected-(U4-ACBUS0-Pad21)") (class "Default")
      (node (ref "U4") (pin "21") (pinfunction "ACBUS0_21") (pintype "bidirectional"))
    )
    (net (code "91") (name "unconnected-(U4-ACBUS1-Pad25)") (class "Default")
      (node (ref "U4") (pin "25") (pinfunction "ACBUS1_25") (pintype "bidirectional"))
    )
    (net (code "92") (name "unconnected-(U4-ACBUS2-Pad26)") (class "Default")
      (node (ref "U4") (pin "26") (pinfunction "ACBUS2_26") (pintype "bidirectional"))
    )
    (net (code "93") (name "unconnected-(U4-ACBUS3-Pad27)") (class "Default")
      (node (ref "U4") (pin "27") (pinfunction "ACBUS3_27") (pintype "bidirectional"))
    )
    (net (code "94") (name "unconnected-(U4-ACBUS4-Pad28)") (class "Default")
      (node (ref "U4") (pin "28") (pinfunction "ACBUS4_28") (pintype "bidirectional"))
    )
    (net (code "95") (name "unconnected-(U4-ACBUS5-Pad29)") (class "Default")
      (node (ref "U4") (pin "29") (pinfunction "ACBUS5_29") (pintype "bidirectional"))
    )
    (net (code "96") (name "unconnected-(U4-ACBUS6-Pad30)") (class "Default")
      (node (ref "U4") (pin "30") (pinfunction "ACBUS6_30") (pintype "bidirectional"))
    )
    (net (code "97") (name "unconnected-(U4-ACBUS7-Pad31)") (class "Default")
      (node (ref "U4") (pin "31") (pinfunction "ACBUS7_31") (pintype "bidirectional"))
    )
    (net (code "98") (name "unconnected-(U4-ACBUS8-Pad32)") (class "Default")
      (node (ref "U4") (pin "32") (pinfunction "ACBUS8_32") (pintype "bidirectional"))
    )
    (net (code "99") (name "unconnected-(U4-ACBUS9-Pad33)") (class "Default")
      (node (ref "U4") (pin "33") (pinfunction "ACBUS9_33") (pintype "bidirectional"))
    )
    (net (code "100") (name "unconnected-(U4-ADBUS5-Pad18)") (class "Default")
      (node (ref "U4") (pin "18") (pinfunction "ADBUS5_18") (pintype "bidirectional"))
    )
    (net (code "101") (name "unconnected-(U4-ADBUS6-Pad19)") (class "Default")
      (node (ref "U4") (pin "19") (pinfunction "ADBUS6_19") (pintype "bidirectional"))
    )
    (net (code "102") (name "unconnected-(U4-ADBUS7-Pad20)") (class "Default")
      (node (ref "U4") (pin "20") (pinfunction "ADBUS7_20") (pintype "bidirectional"))
    )
    (net (code "103") (name "unconnected-(U4-EECLK-Pad44)") (class "Default")
      (node (ref "U4") (pin "44") (pinfunction "EECLK_44") (pintype "bidirectional"))
    )
    (net (code "104") (name "unconnected-(U4-EECS-Pad45)") (class "Default")
      (node (ref "U4") (pin "45") (pinfunction "EECS_45") (pintype "bidirectional"))
    )
    (net (code "105") (name "unconnected-(U4-EEDATA-Pad43)") (class "Default")
      (node (ref "U4") (pin "43") (pinfunction "EEDATA_43") (pintype "bidirectional"))
    )
    (net (code "106") (name "~{DW_CS}") (class "Default")
      (node (ref "J2") (pin "5") (pinfunction "5_5") (pintype "passive"))
      (node (ref "U1") (pin "23") (pinfunction "~{DEBUG_DW_CS}_23") (pintype "bidirectional"))
    )
    (net (code "107") (name "~{DW_RST}") (class "Default")
      (node (ref "J2") (pin "6") (pinfunction "6_6") (pintype "passive"))
      (node (ref "U1") (pin "24") (pinfunction "~{DEBUG_DW_RST}_24") (pintype "bidirectional"))
    )
  )
)
